# ffcbreakout.net
KiCad netlist of a schematic drawn in EAGLE
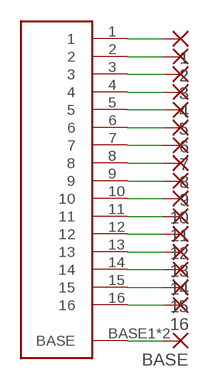
[diagram p0: schematic, sheet 1]

(export (version "E")
  (design (tool "Eeschema 10.0.6"))
  (components
    (comp (ref "1")
      (value "1,6/0,8")
      (footprint "eagle-import:1,6_0,8")
      (libsource (lib "eagle-import") (part "1,6/0,8"))
    )
    (comp (ref "2")
      (value "1,6/0,8")
      (footprint "eagle-import:1,6_0,8")
      (libsource (lib "eagle-import") (part "1,6/0,8"))
    )
    (comp (ref "3")
      (value "1,6/0,8")
      (footprint "eagle-import:1,6_0,8")
      (libsource (lib "eagle-import") (part "1,6/0,8"))
    )
    (comp (ref "4")
      (value "1,6/0,8")
      (footprint "eagle-import:1,6_0,8")
      (libsource (lib "eagle-import") (part "1,6/0,8"))
    )
    (comp (ref "5")
      (value "1,6/0,8")
      (footprint "eagle-import:1,6_0,8")
      (libsource (lib "eagle-import") (part "1,6/0,8"))
    )
    (comp (ref "6")
      (value "1,6/0,8")
      (footprint "eagle-import:1,6_0,8")
      (libsource (lib "eagle-import") (part "1,6/0,8"))
    )
    (comp (ref "7")
      (value "1,6/0,8")
      (footprint "eagle-import:1,6_0,8")
      (libsource (lib "eagle-import") (part "1,6/0,8"))
    )
    (comp (ref "8")
      (value "1,6/0,8")
      (footprint "eagle-import:1,6_0,8")
      (libsource (lib "eagle-import") (part "1,6/0,8"))
    )
    (comp (ref "9")
      (value "1,6/0,8")
      (footprint "eagle-import:1,6_0,8")
      (libsource (lib "eagle-import") (part "1,6/0,8"))
    )
    (comp (ref "10")
      (value "1,6/0,8")
      (footprint "eagle-import:1,6_0,8")
      (libsource (lib "eagle-import") (part "1,6/0,8"))
    )
    (comp (ref "11")
      (value "1,6/0,8")
      (footprint "eagle-import:1,6_0,8")
      (libsource (lib "eagle-import") (part "1,6/0,8"))
    )
    (comp (ref "12")
      (value "1,6/0,8")
      (footprint "eagle-import:1,6_0,8")
      (libsource (lib "eagle-import") (part "1,6/0,8"))
    )
    (comp (ref "13")
      (value "1,6/0,8")
      (footprint "eagle-import:1,6_0,8")
      (libsource (lib "eagle-import") (part "1,6/0,8"))
    )
    (comp (ref "14")
      (value "1,6/0,8")
      (footprint "eagle-import:1,6_0,8")
      (libsource (lib "eagle-import") (part "1,6/0,8"))
    )
    (comp (ref "15")
      (value "1,6/0,8")
      (footprint "eagle-import:1,6_0,8")
      (libsource (lib "eagle-import") (part "1,6/0,8"))
    )
    (comp (ref "16")
      (value "1,6/0,8")
      (footprint "eagle-import:1,6_0,8")
      (libsource (lib "eagle-import") (part "1,6/0,8"))
    )
    (comp (ref "BASE")
      (value "1,6/0,8")
      (footprint "eagle-import:1,6_0,8")
      (libsource (lib "eagle-import") (part "1,6/0,8"))
    )
    (comp (ref "U$1")
      (value "16PINFFC")
      (footprint "eagle-import:16PINFFC")
      (libsource (lib "eagle-import") (part "16PINFFC"))
    )
  )
  (nets
    (net (code "1") (name "Net-(1-P)") (class "Default")
      (node (ref "1") (pin "1") (pinfunction "P_1") (pintype "passive"))
      (node (ref "U$1") (pin "1") (pinfunction "1_1") (pintype "bidirectional"))
    )
    (net (code "2") (name "Net-(2-P)") (class "Default")
      (node (ref "2") (pin "1") (pinfunction "P_1") (pintype "passive"))
      (node (ref "U$1") (pin "2") (pinfunction "2_2") (pintype "bidirectional"))
    )
    (net (code "3") (name "Net-(3-P)") (class "Default")
      (node (ref "3") (pin "1") (pinfunction "P_1") (pintype "passive"))
      (node (ref "U$1") (pin "3") (pinfunction "3_3") (pintype "bidirectional"))
    )
    (net (code "4") (name "Net-(4-P)") (class "Default")
      (node (ref "4") (pin "1") (pinfunction "P_1") (pintype "passive"))
      (node (ref "U$1") (pin "4") (pinfunction "4_4") (pintype "bidirectional"))
    )
    (net (code "5") (name "Net-(5-P)") (class "Default")
      (node (ref "5") (pin "1") (pinfunction "P_1") (pintype "passive"))
      (node (ref "U$1") (pin "5") (pinfunction "5_5") (pintype "bidirectional"))
    )
    (net (code "6") (name "Net-(6-P)") (class "Default")
      (node (ref "6") (pin "1") (pinfunction "P_1") (pintype "passive"))
      (node (ref "U$1") (pin "6") (pinfunction "6_6") (pintype "bidirectional"))
    )
    (net (code "7") (name "Net-(7-P)") (class "Default")
      (node (ref "7") (pin "1") (pinfunction "P_1") (pintype "passive"))
      (node (ref "U$1") (pin "7") (pinfunction "7_7") (pintype "bidirectional"))
    )
    (net (code "8") (name "Net-(8-P)") (class "Default")
      (node (ref "8") (pin "1") (pinfunction "P_1") (pintype "passive"))
      (node (ref "U$1") (pin "8") (pinfunction "8_8") (pintype "bidirectional"))
    )
    (net (code "9") (name "Net-(9-P)") (class "Default")
      (node (ref "9") (pin "1") (pinfunction "P_1") (pintype "passive"))
      (node (ref "U$1") (pin "9") (pinfunction "9_9") (pintype "bidirectional"))
    )
    (net (code "10") (name "Net-(10-P)") (class "Default")
      (node (ref "10") (pin "1") (pinfunction "P_1") (pintype "passive"))
      (node (ref "U$1") (pin "10") (pinfunction "10_10") (pintype "bidirectional"))
    )
    (net (code "11") (name "Net-(11-P)") (class "Default")
      (node (ref "11") (pin "1") (pinfunction "P_1") (pintype "passive"))
      (node (ref "U$1") (pin "11") (pinfunction "11_11") (pintype "bidirectional"))
    )
    (net (code "12") (name "Net-(12-P)") (class "Default")
      (node (ref "12") (pin "1") (pinfunction "P_1") (pintype "passive"))
      (node (ref "U$1") (pin "12") (pinfunction "12_12") (pintype "bidirectional"))
    )
    (net (code "13") (name "Net-(13-P)") (class "Default")
      (node (ref "13") (pin "1") (pinfunction "P_1") (pintype "passive"))
      (node (ref "U$1") (pin "13") (pinfunction "13_13") (pintype "bidirectional"))
    )
    (net (code "14") (name "Net-(14-P)") (class "Default")
      (node (ref "14") (pin "1") (pinfunction "P_1") (pintype "passive"))
      (node (ref "U$1") (pin "14") (pinfunction "14_14") (pintype "bidirectional"))
    )
    (net (code "15") (name "Net-(15-P)") (class "Default")
      (node (ref "15") (pin "1") (pinfunction "P_1") (pintype "passive"))
      (node (ref "U$1") (pin "15") (pinfunction "15_15") (pintype "bidirectional"))
    )
    (net (code "16") (name "Net-(16-P)") (class "Default")
      (node (ref "16") (pin "1") (pinfunction "P_1") (pintype "passive"))
      (node (ref "U$1") (pin "16") (pinfunction "16_16") (pintype "bidirectional"))
    )
    (net (code "17") (name "Net-(BASE-P)") (class "Default")
      (node (ref "BASE") (pin "1") (pinfunction "P_1") (pintype "passive"))
      (node (ref "U$1") (pin "BASE1") (pinfunction "BASE_BASE1") (pintype "bidirectional"))
      (node (ref "U$1") (pin "BASE2") (pinfunction "BASE_BASE2") (pintype "bidirectional"))
    )
  )
)
